# remote_2313_4313.net
KiCad netlist of a schematic drawn in EAGLE
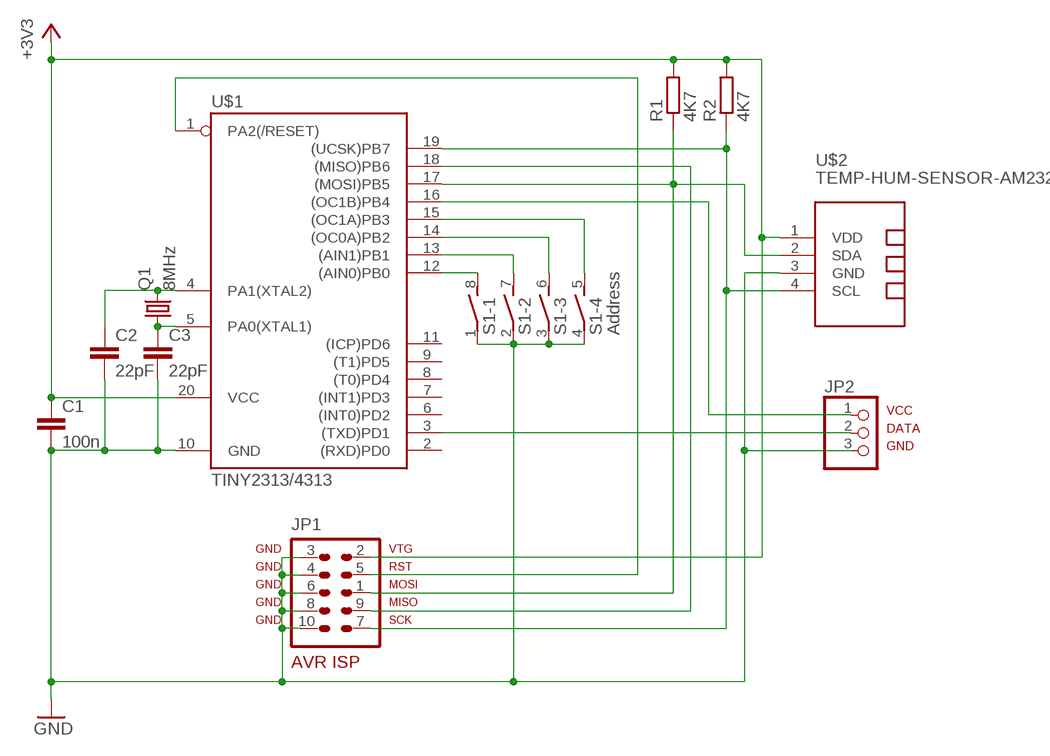
[diagram p0: schematic, sheet 1]

(export (version "E")
  (design (tool "Eeschema 10.0.6"))
  (components
    (comp (ref "C1")
      (value "100n")
      (footprint "eagle-import:C025-025X050")
      (libsource (lib "eagle-import") (part "C-EU025-025X050"))
    )
    (comp (ref "C2")
      (value "22pF")
      (footprint "eagle-import:C025-024X044")
      (libsource (lib "eagle-import") (part "C-EU025-024X044"))
    )
    (comp (ref "C3")
      (value "22pF")
      (footprint "eagle-import:C025-024X044")
      (libsource (lib "eagle-import") (part "C-EU025-024X044"))
    )
    (comp (ref "JP1")
      (value "AVR-ISP-10")
      (footprint "eagle-import:AVR-ISP-10")
      (libsource (lib "eagle-import") (part "AVR-ISP-10"))
    )
    (comp (ref "JP2")
      (value "PINHD-1X3")
      (footprint "eagle-import:1X03")
      (libsource (lib "eagle-import") (part "PINHD-1X3"))
    )
    (comp (ref "Q1")
      (value "8MHz")
      (footprint "eagle-import:HC49U-V")
      (libsource (lib "eagle-import") (part "CRYSTALHC49U-V"))
    )
    (comp (ref "R1")
      (value "4K7")
      (footprint "eagle-import:0204_5")
      (libsource (lib "eagle-import") (part "R-EU_0204/5"))
    )
    (comp (ref "R2")
      (value "4K7")
      (footprint "eagle-import:0204_5")
      (libsource (lib "eagle-import") (part "R-EU_0204/5"))
    )
    (comp (ref "S1")
      (value "Address")
      (footprint "eagle-import:DIP04S")
      (libsource (lib "eagle-import") (part "DIP04S"))
    )
    (comp (ref "U$1")
      (value "TINY2313/4313")
      (footprint "eagle-import:DIL20")
      (libsource (lib "eagle-import") (part "TINY2313-P"))
    )
    (comp (ref "U$2")
      (value "TEMP-HUM-SENSOR-AM2322")
      (footprint "eagle-import:TEMP-HUM-SENSOR-AM2322")
      (libsource (lib "eagle-import") (part "TEMP-HUM-SENSOR-AM2322"))
    )
  )
  (nets
    (net (code "1") (name "+3V3") (class "Default")
      (node (ref "C1") (pin "1") (pinfunction "1_1") (pintype "passive"))
      (node (ref "JP1") (pin "2") (pinfunction "2_2") (pintype "passive"))
      (node (ref "R1") (pin "2") (pinfunction "2_2") (pintype "passive"))
      (node (ref "R2") (pin "2") (pinfunction "2_2") (pintype "passive"))
      (node (ref "U$1") (pin "20") (pinfunction "VCC_20") (pintype "power_in"))
      (node (ref "U$2") (pin "1") (pinfunction "VDD_1") (pintype "power_in"))
    )
    (net (code "2") (name "GND") (class "Default")
      (node (ref "C1") (pin "2") (pinfunction "2_2") (pintype "passive"))
      (node (ref "C2") (pin "2") (pinfunction "2_2") (pintype "passive"))
      (node (ref "C3") (pin "2") (pinfunction "2_2") (pintype "passive"))
      (node (ref "JP1") (pin "10") (pinfunction "10_10") (pintype "passive"))
      (node (ref "JP1") (pin "3") (pinfunction "3_3") (pintype "passive"))
      (node (ref "JP1") (pin "4") (pinfunction "4_4") (pintype "passive"))
      (node (ref "JP1") (pin "6") (pinfunction "6_6") (pintype "passive"))
      (node (ref "JP1") (pin "8") (pinfunction "8_8") (pintype "passive"))
      (node (ref "JP2") (pin "3") (pinfunction "3_3") (pintype "passive"))
      (node (ref "S1") (pin "1") (pinfunction "1_1") (pintype "passive"))
      (node (ref "S1") (pin "2") (pinfunction "1_2") (pintype "passive"))
      (node (ref "S1") (pin "3") (pinfunction "1_3") (pintype "passive"))
      (node (ref "S1") (pin "4") (pinfunction "1_4") (pintype "passive"))
      (node (ref "U$1") (pin "10") (pinfunction "GND_10") (pintype "power_in"))
      (node (ref "U$2") (pin "3") (pinfunction "GND_3") (pintype "power_in"))
    )
    (net (code "3") (name "Net-(S1A-2)") (class "Default")
      (node (ref "S1") (pin "8") (pinfunction "2_8") (pintype "passive"))
      (node (ref "U$1") (pin "12") (pinfunction "(AIN0)PB0_12") (pintype "bidirectional"))
    )
    (net (code "4") (name "Net-(S1B-2)") (class "Default")
      (node (ref "S1") (pin "7") (pinfunction "2_7") (pintype "passive"))
      (node (ref "U$1") (pin "13") (pinfunction "(AIN1)PB1_13") (pintype "bidirectional"))
    )
    (net (code "5") (name "Net-(S1C-2)") (class "Default")
      (node (ref "S1") (pin "6") (pinfunction "2_6") (pintype "passive"))
      (node (ref "U$1") (pin "14") (pinfunction "(OC0A)PB2_14") (pintype "bidirectional"))
    )
    (net (code "6") (name "Net-(S1D-2)") (class "Default")
      (node (ref "S1") (pin "5") (pinfunction "2_5") (pintype "passive"))
      (node (ref "U$1") (pin "15") (pinfunction "(OC1A)PB3_15") (pintype "bidirectional"))
    )
    (net (code "7") (name "Net-(U$1-(MISO)PB6)") (class "Default")
      (node (ref "JP1") (pin "9") (pinfunction "9_9") (pintype "passive"))
      (node (ref "U$1") (pin "18") (pinfunction "(MISO)PB6_18") (pintype "bidirectional"))
    )
    (net (code "8") (name "Net-(U$1-(MOSI)PB5)") (class "Default")
      (node (ref "JP1") (pin "1") (pinfunction "1_1") (pintype "passive"))
      (node (ref "R1") (pin "1") (pinfunction "1_1") (pintype "passive"))
      (node (ref "U$1") (pin "17") (pinfunction "(MOSI)PB5_17") (pintype "bidirectional"))
      (node (ref "U$2") (pin "2") (pinfunction "SDA_2") (pintype "bidirectional"))
    )
    (net (code "9") (name "Net-(U$1-(OC1B)PB4)") (class "Default")
      (node (ref "JP2") (pin "1") (pinfunction "1_1") (pintype "passive"))
      (node (ref "U$1") (pin "16") (pinfunction "(OC1B)PB4_16") (pintype "bidirectional"))
    )
    (net (code "10") (name "Net-(U$1-(TXD)PD1)") (class "Default")
      (node (ref "JP2") (pin "2") (pinfunction "2_2") (pintype "passive"))
      (node (ref "U$1") (pin "3") (pinfunction "(TXD)PD1_3") (pintype "bidirectional"))
    )
    (net (code "11") (name "Net-(U$1-(UCSK)PB7)") (class "Default")
      (node (ref "JP1") (pin "7") (pinfunction "7_7") (pintype "passive"))
      (node (ref "R2") (pin "1") (pinfunction "1_1") (pintype "passive"))
      (node (ref "U$1") (pin "19") (pinfunction "(UCSK)PB7_19") (pintype "bidirectional"))
      (node (ref "U$2") (pin "4") (pinfunction "SCL_4") (pintype "bidirectional"))
    )
    (net (code "12") (name "Net-(U$1-PA0(XTAL1))") (class "Default")
      (node (ref "C3") (pin "1") (pinfunction "1_1") (pintype "passive"))
      (node (ref "Q1") (pin "1") (pinfunction "1_1") (pintype "passive"))
      (node (ref "U$1") (pin "5") (pinfunction "PA0(XTAL1)_5") (pintype "bidirectional"))
    )
    (net (code "13") (name "Net-(U$1-PA1(XTAL2))") (class "Default")
      (node (ref "C2") (pin "1") (pinfunction "1_1") (pintype "passive"))
      (node (ref "Q1") (pin "2") (pinfunction "2_2") (pintype "passive"))
      (node (ref "U$1") (pin "4") (pinfunction "PA1(XTAL2)_4") (pintype "bidirectional"))
    )
    (net (code "14") (name "Net-(U$1-PA2({slash}RESET))") (class "Default")
      (node (ref "JP1") (pin "5") (pinfunction "5_5") (pintype "passive"))
      (node (ref "U$1") (pin "1") (pinfunction "PA2(/RESET)_1") (pintype "input"))
    )
    (net (code "15") (name "unconnected-(U$1-(ICP)PD6-Pad11)") (class "Default")
      (node (ref "U$1") (pin "11") (pinfunction "(ICP)PD6_11") (pintype "bidirectional"))
    )
    (net (code "16") (name "unconnected-(U$1-(INT0)PD2-Pad6)") (class "Default")
      (node (ref "U$1") (pin "6") (pinfunction "(INT0)PD2_6") (pintype "bidirectional"))
    )
    (net (code "17") (name "unconnected-(U$1-(INT1)PD3-Pad7)") (class "Default")
      (node (ref "U$1") (pin "7") (pinfunction "(INT1)PD3_7") (pintype "bidirectional"))
    )
    (net (code "18") (name "unconnected-(U$1-(RXD)PD0-Pad2)") (class "Default")
      (node (ref "U$1") (pin "2") (pinfunction "(RXD)PD0_2") (pintype "bidirectional"))
    )
    (net (code "19") (name "unconnected-(U$1-(T0)PD4-Pad8)") (class "Default")
      (node (ref "U$1") (pin "8") (pinfunction "(T0)PD4_8") (pintype "bidirectional"))
    )
    (net (code "20") (name "unconnected-(U$1-(T1)PD5-Pad9)") (class "Default")
      (node (ref "U$1") (pin "9") (pinfunction "(T1)PD5_9") (pintype "bidirectional"))
    )
  )
)
